# fm_transmitter.net
KiCad netlist of a schematic drawn in Altium Designer
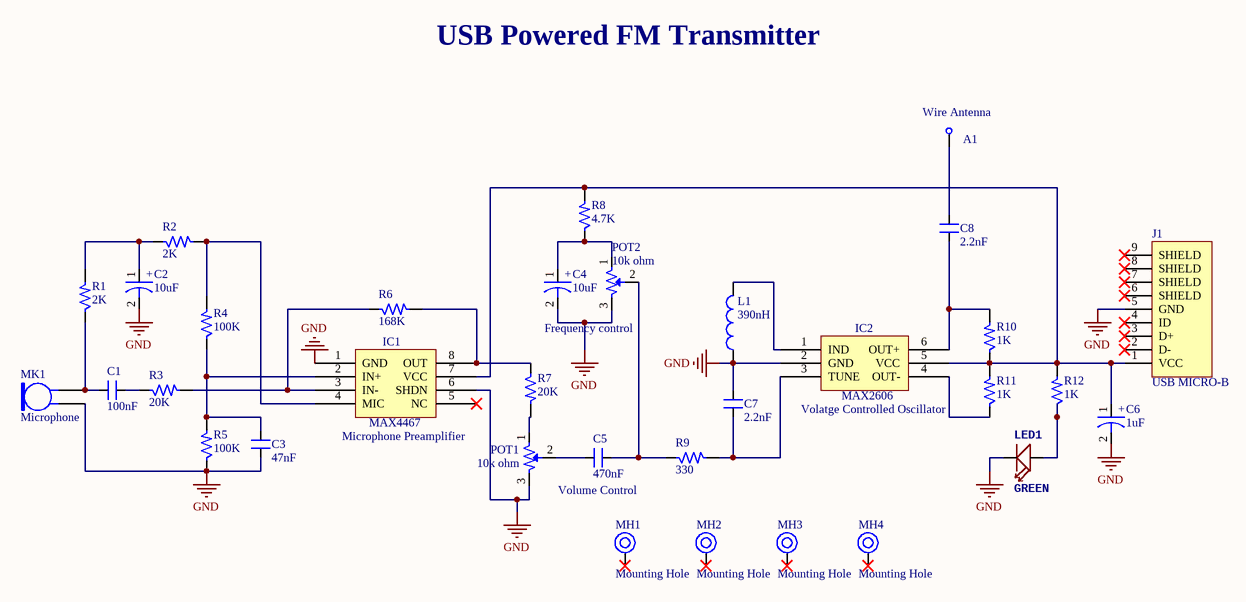
[diagram p0: fm_transmitter.SchDoc]

(export (version "E")
  (design (tool "Eeschema 10.0.6"))
  (components
    (comp (ref "A1")
      (value "Wire Antenna")
      (footprint "TEST POINT_78")
      (description "0.4mm hole size Test point")
      (fields (field (name "MANUFACTURER PART NUMBER") "NA"))
      (libsource (lib "ESTEEMPCBLIB") (part "TEST POINT"))
    )
    (comp (ref "C1")
      (value "100nF")
      (footprint "CAP_0805")
      (description "0.1µF ±10% 50V Ceramic Capacitor X7R 0805 (2012 Metric)")
      (fields
        (field (name "MANUFACTURER") "Samsung")
        (field (name "MANUFACTURER PART NUMBER") "CL21B104KBCNNNC")
      )
      (libsource (lib "ESTEEMPCBLIB") (part "CAP_0.1uF-50V-10%-0805"))
    )
    (comp (ref "C2")
      (value "10uF")
      (footprint "ACAP_P339_D393_H531_RAD")
      (description "10µF 400V Aluminum Electrolytic Capacitors Radial, Can - SMD 10000 Hrs @ 105°C")
      (fields
        (field (name "MANUFACTURER") "Nichicon")
        (field (name "MANUFACTURER PART NUMBER") "ULV2G100MNL1GS")
      )
      (libsource (lib "ESTEEMPCBLIB") (part "CAP-P_10uF-400V-20%-RAD"))
    )
    (comp (ref "C3")
      (value "47nF")
      (footprint "CAP_0805")
      (description "0.1µF ±10% 50V Ceramic Capacitor X7R 0805 (2012 Metric)")
      (fields
        (field (name "MANUFACTURER") "Samsung")
        (field (name "MANUFACTURER PART NUMBER") "CL21B104KBCNNNC")
      )
      (libsource (lib "ESTEEMPCBLIB") (part "CAP_0.1uF-50V-10%-0805"))
    )
    (comp (ref "C4")
      (value "10uF")
      (footprint "ACAP_P339_D393_H531_RAD")
      (description "10µF 400V Aluminum Electrolytic Capacitors Radial, Can - SMD 10000 Hrs @ 105°C")
      (fields
        (field (name "MANUFACTURER") "Nichicon")
        (field (name "MANUFACTURER PART NUMBER") "ULV2G100MNL1GS")
      )
      (libsource (lib "ESTEEMPCBLIB") (part "CAP-P_10uF-400V-20%-RAD"))
    )
    (comp (ref "C5")
      (value "470nF")
      (footprint "CAP_0805")
      (description "0.1µF ±10% 50V Ceramic Capacitor X7R 0805 (2012 Metric)")
      (fields
        (field (name "MANUFACTURER") "Samsung")
        (field (name "MANUFACTURER PART NUMBER") "CL21B104KBCNNNC")
      )
      (libsource (lib "ESTEEMPCBLIB") (part "CAP_0.1uF-50V-10%-0805"))
    )
    (comp (ref "C6")
      (value "1uF")
      (footprint "ACAP_P339_D393_H531_RAD")
      (description "10µF 400V Aluminum Electrolytic Capacitors Radial, Can - SMD 10000 Hrs @ 105°C")
      (fields
        (field (name "MANUFACTURER") "Nichicon")
        (field (name "MANUFACTURER PART NUMBER") "ULV2G100MNL1GS")
      )
      (libsource (lib "ESTEEMPCBLIB") (part "CAP-P_10uF-400V-20%-RAD"))
    )
    (comp (ref "C7")
      (value "2.2nF")
      (footprint "CAP_0805")
      (description "0.1µF ±10% 50V Ceramic Capacitor X7R 0805 (2012 Metric)")
      (fields
        (field (name "MANUFACTURER") "Samsung")
        (field (name "MANUFACTURER PART NUMBER") "CL21B104KBCNNNC")
      )
      (libsource (lib "ESTEEMPCBLIB") (part "CAP_0.1uF-50V-10%-0805"))
    )
    (comp (ref "C8")
      (value "2.2nF")
      (footprint "CAP_0805")
      (description "0.1µF ±10% 50V Ceramic Capacitor X7R 0805 (2012 Metric)")
      (fields
        (field (name "MANUFACTURER") "Samsung")
        (field (name "MANUFACTURER PART NUMBER") "CL21B104KBCNNNC")
      )
      (libsource (lib "ESTEEMPCBLIB") (part "CAP_0.1uF-50V-10%-0805"))
    )
    (comp (ref "IC1")
      (value "MAX4467")
      (footprint "TI SOT-23-8 DDF")
      (libsource (lib "MAX_ICs") (part "IC_MAX4467"))
    )
    (comp (ref "IC2")
      (value "MAX2606")
      (footprint "MAXIM SOT-23-6")
      (libsource (lib "MAX_ICs") (part "IC_MAX2606"))
    )
    (comp (ref "J1")
      (value "USB MICRO-B")
      (footprint "CON_10118192-0001LF_SMD")
      (description "USB - micro B USB 2.0 Receptacle Connector 5 Position Surface Mount, Right Angle")
      (fields (field (name "MANUFACTURER") "ICC") (field (name "MANUFACTURER PART NUMBER") "10118192-0001LF"))
      (libsource (lib "ESTEEMPCBLIB") (part "CON_USB2.0_MICROB-SMD"))
    )
    (comp (ref "L1")
      (value "390nH")
      (footprint "IND_0805")
      (description "Fixed Inductors MSS1583 SMT Power 0.038Ohms 33uH")
      (fields
        (field (name "MANUFACTURER") "Coilcraft")
        (field (name "MANUFACTURER PART NUMBER") "MSS1583-333MEB")
      )
      (libsource (lib "ESTEEMPCBLIB") (part "IND_33uH-8A-20%-SMD"))
    )
    (comp (ref "LED1")
      (value "GREEN")
      (footprint "LED-0603")
      (fields (field (name "MPN") "19-217-R6C-AL1M2VY-3T"))
      (libsource (lib "AltiumLibraryDDT") (part "LED-SMD-RED-DIFFUSED(0603)"))
    )
    (comp (ref "MH1")
      (value "Mounting Hole")
      (footprint "MOUNTING")
      (fields (field (name "MANUFACTURER PART NUMBER") "NA"))
      (libsource (lib "ESTEEMPCBLIB") (part "MH_3.5H_6D"))
    )
    (comp (ref "MH2")
      (value "Mounting Hole")
      (footprint "MOUNTING")
      (fields (field (name "MANUFACTURER PART NUMBER") "NA"))
      (libsource (lib "ESTEEMPCBLIB") (part "MH_3.5H_6D"))
    )
    (comp (ref "MH3")
      (value "Mounting Hole")
      (footprint "MOUNTING")
      (fields (field (name "MANUFACTURER PART NUMBER") "NA"))
      (libsource (lib "ESTEEMPCBLIB") (part "MH_3.5H_6D"))
    )
    (comp (ref "MH4")
      (value "Mounting Hole")
      (footprint "MOUNTING")
      (fields (field (name "MANUFACTURER PART NUMBER") "NA"))
      (libsource (lib "ESTEEMPCBLIB") (part "MH_3.5H_6D"))
    )
    (comp (ref "MK1")
      (value "Microphone")
      (footprint "PIN2")
      (fields (field (name "PUBLISHER") "Altium Limited"))
      (libsource (lib "Miscellaneous Devices") (part "Mic2"))
    )
    (comp (ref "POT1")
      (value "10k ohm")
      (footprint "POT_3361P_SMD")
      (description "10 kOhms 0.5W, 1/2W Gull Wing Surface Mount Trimmer Potentiometer Cermet 1 Turn Top Adjustment")
      (fields
        (field (name "MANUFACTURER") "Bourns")
        (field (name "MANUFACTURER PART NUMBER") "3361P-1-103GLF")
      )
      (libsource (lib "ESTEEMPCBLIB") (part "POT_10K-3361P-1-103GLF-SMD"))
    )
    (comp (ref "POT2")
      (value "10k ohm")
      (footprint "POT_3361P_SMD")
      (description "10 kOhms 0.5W, 1/2W Gull Wing Surface Mount Trimmer Potentiometer Cermet 1 Turn Top Adjustment")
      (fields
        (field (name "MANUFACTURER") "Bourns")
        (field (name "MANUFACTURER PART NUMBER") "3361P-1-103GLF")
      )
      (libsource (lib "ESTEEMPCBLIB") (part "POT_10K-3361P-1-103GLF-SMD"))
    )
    (comp (ref "R1")
      (value "2K")
      (footprint "RES_0805")
      (description "2 kOhms ±1% 0.125W, 1/8W Chip Resistor 0805 (2012 Metric) Moisture Resistant Thick Film")
      (fields
        (field (name "MANUFACTURER") "TE Connectivity")
        (field (name "MANUFACTURER PART NUMBER") "RC0805FR-072KL")
      )
      (libsource (lib "ESTEEMPCBLIB") (part "RES_2K-0.125W-1%-0805"))
    )
    (comp (ref "R2")
      (value "2K")
      (footprint "RES_0805")
      (description "2 kOhms ±1% 0.125W, 1/8W Chip Resistor 0805 (2012 Metric) Moisture Resistant Thick Film")
      (fields
        (field (name "MANUFACTURER") "TE Connectivity")
        (field (name "MANUFACTURER PART NUMBER") "RC0805FR-072KL")
      )
      (libsource (lib "ESTEEMPCBLIB") (part "RES_2K-0.125W-1%-0805"))
    )
    (comp (ref "R3")
      (value "20K")
      (footprint "RES_0805")
      (fields
        (field (name "MANUFACTURER") "Panasonic")
        (field (name "MANUFACTURER PART NUMBER") "ERJ-P06J203V")
      )
      (libsource (lib "ESTEEMPCBLIB") (part "RES_20K-0.5W-5%-0805"))
    )
    (comp (ref "R4")
      (value "100K")
      (footprint "RES_0805")
      (description "100 kOhms ±1% 0.125W, 1/8W Chip Resistor 0805 (2012 Metric) Automotive AEC-Q200 Thick Film")
      (fields (field (name "MANUFACTURER") "Walsin") (field (name "MANUFACTURER PART NUMBER") "WR08X1003FTL"))
      (libsource (lib "ESTEEMPCBLIB") (part "RES_100K-0.125W-1%-0805"))
    )
    (comp (ref "R5")
      (value "100K")
      (footprint "RES_0805")
      (description "100 kOhms ±1% 0.125W, 1/8W Chip Resistor 0805 (2012 Metric) Automotive AEC-Q200 Thick Film")
      (fields (field (name "MANUFACTURER") "Walsin") (field (name "MANUFACTURER PART NUMBER") "WR08X1003FTL"))
      (libsource (lib "ESTEEMPCBLIB") (part "RES_100K-0.125W-1%-0805"))
    )
    (comp (ref "R6")
      (value "168K")
      (footprint "RES_0805")
      (description "168 kOhms ±1% 0.125W, 1/8W Chip Resistor 0805 (2012 Metric) Automotive AEC-Q200 Thick Film")
      (fields (field (name "MANUFACTURER") "Walsin") (field (name "MANUFACTURER PART NUMBER") "WR08X1003FTL"))
      (libsource (lib "ESTEEMPCBLIB") (part "RES_100K-0.125W-1%-0805"))
    )
    (comp (ref "R7")
      (value "20K")
      (footprint "RES_0805")
      (fields
        (field (name "MANUFACTURER") "Panasonic")
        (field (name "MANUFACTURER PART NUMBER") "ERJ-P06J203V")
      )
      (libsource (lib "ESTEEMPCBLIB") (part "RES_20K-0.5W-5%-0805"))
    )
    (comp (ref "R8")
      (value "4.7K")
      (footprint "RES_0805")
      (description "4.7 kOhms ±1% 0.125W, 1/8W Chip Resistor 0805 (2012 Metric) Moisture Resistant Thick Film")
      (fields
        (field (name "MANUFACTURER") "TE Connectivity")
        (field (name "MANUFACTURER PART NUMBER") "RC0805FR-074K7L")
      )
      (libsource (lib "ESTEEMPCBLIB") (part "RES_4.7K-0.125W-1%-0805"))
    )
    (comp (ref "R9")
      (value "330")
      (footprint "RES_0805")
      (description "300 Ohms ±1% 0.125W, 1/8W Chip Resistor 0805 (2012 Metric) Thick Film")
      (fields (field (name "MANUFACTURER") "Panasonic") (field (name "MANUFACTURER PART NUMBER") "1623214-1"))
      (libsource (lib "ESTEEMPCBLIB") (part "RES_3.3K-0.125W-1%-0805"))
    )
    (comp (ref "R10")
      (value "1K")
      (footprint "RES_0805")
      (description "1 kOhms ±1% 0.125W, 1/8W Chip Resistor 0805 (2012 Metric) Moisture Resistant Thick Film")
      (fields (field (name "MANUFACTURER") "Walsin") (field (name "MANUFACTURER PART NUMBER") "WR08X1001FTL"))
      (libsource (lib "ESTEEMPCBLIB") (part "RES_1K-0.125W-1%-0805"))
    )
    (comp (ref "R11")
      (value "1K")
      (footprint "RES_0805")
      (description "10 kOhms ±1% 0.125W, 1/8W Chip Resistor 0805 (2012 Metric) Automotive AEC-Q200 Thick Film")
      (fields (field (name "MANUFACTURER") "CTS") (field (name "MANUFACTURER PART NUMBER") "WR08X1002FTL"))
      (libsource (lib "ESTEEMPCBLIB") (part "RES_10K-0.125W-1%-0805"))
    )
    (comp (ref "R12")
      (value "1K")
      (footprint "RES_0805")
      (description "1 kOhms ±1% 0.125W, 1/8W Chip Resistor 0805 (2012 Metric) Moisture Resistant Thick Film")
      (fields (field (name "MANUFACTURER") "Walsin") (field (name "MANUFACTURER PART NUMBER") "WR08X1001FTL"))
      (libsource (lib "ESTEEMPCBLIB") (part "RES_1K-0.125W-1%-0805"))
    )
  )
  (nets
    (net (code "1") (name "GND") (class "Default")
      (node (ref "C2") (pin "2") (pinfunction "2_2") (pintype "passive"))
      (node (ref "C3") (pin "1") (pinfunction "1_1") (pintype "passive"))
      (node (ref "C4") (pin "2") (pinfunction "2_2") (pintype "passive"))
      (node (ref "C6") (pin "2") (pinfunction "2_2") (pintype "passive"))
      (node (ref "C7") (pin "2") (pinfunction "2_2") (pintype "passive"))
      (node (ref "IC1") (pin "1") (pinfunction "GND_1") (pintype "passive"))
      (node (ref "IC1") (pin "6") (pinfunction "SHDN_6") (pintype "passive"))
      (node (ref "IC2") (pin "2") (pinfunction "GND_2") (pintype "passive"))
      (node (ref "J1") (pin "5") (pinfunction "GND_5") (pintype "passive"))
      (node (ref "L1") (pin "1") (pinfunction "1_1") (pintype "passive"))
      (node (ref "LED1") (pin "-") (pinfunction "-_-") (pintype "passive"))
      (node (ref "MK1") (pin "1") (pinfunction "1_1") (pintype "passive"))
      (node (ref "POT1") (pin "3") (pinfunction "3_3") (pintype "passive"))
      (node (ref "POT2") (pin "3") (pinfunction "3_3") (pintype "passive"))
      (node (ref "R5") (pin "1") (pinfunction "1_1") (pintype "passive"))
    )
    (net (code "2") (name "Net-(A1-Pad1)") (class "Default")
      (node (ref "A1") (pin "1") (pinfunction "1_1") (pintype "passive"))
      (node (ref "C8") (pin "2") (pinfunction "2_2") (pintype "passive"))
    )
    (net (code "3") (name "Net-(C1-Pad1)") (class "Default")
      (node (ref "C1") (pin "1") (pinfunction "1_1") (pintype "passive"))
      (node (ref "MK1") (pin "2") (pinfunction "2_2") (pintype "passive"))
      (node (ref "R1") (pin "1") (pinfunction "1_1") (pintype "passive"))
    )
    (net (code "4") (name "Net-(C1-Pad2)") (class "Default")
      (node (ref "C1") (pin "2") (pinfunction "2_2") (pintype "passive"))
      (node (ref "R3") (pin "1") (pinfunction "1_1") (pintype "passive"))
    )
    (net (code "5") (name "Net-(C2-Pad1)") (class "Default")
      (node (ref "C2") (pin "1") (pinfunction "1_1") (pintype "passive"))
      (node (ref "R1") (pin "2") (pinfunction "2_2") (pintype "passive"))
      (node (ref "R2") (pin "1") (pinfunction "1_1") (pintype "passive"))
    )
    (net (code "6") (name "Net-(C4-Pad1)") (class "Default")
      (node (ref "C4") (pin "1") (pinfunction "1_1") (pintype "passive"))
      (node (ref "POT2") (pin "1") (pinfunction "1_1") (pintype "passive"))
      (node (ref "R8") (pin "1") (pinfunction "1_1") (pintype "passive"))
    )
    (net (code "7") (name "Net-(C5-Pad1)") (class "Default")
      (node (ref "C5") (pin "1") (pinfunction "1_1") (pintype "passive"))
      (node (ref "POT1") (pin "2") (pinfunction "2_2") (pintype "passive"))
    )
    (net (code "8") (name "Net-(C5-Pad2)") (class "Default")
      (node (ref "C5") (pin "2") (pinfunction "2_2") (pintype "passive"))
      (node (ref "POT2") (pin "2") (pinfunction "2_2") (pintype "passive"))
      (node (ref "R9") (pin "1") (pinfunction "1_1") (pintype "passive"))
    )
    (net (code "9") (name "Net-(IC1-IN+)") (class "Default")
      (node (ref "C3") (pin "2") (pinfunction "2_2") (pintype "passive"))
      (node (ref "IC1") (pin "2") (pinfunction "IN+_2") (pintype "passive"))
      (node (ref "R4") (pin "1") (pinfunction "1_1") (pintype "passive"))
      (node (ref "R5") (pin "2") (pinfunction "2_2") (pintype "passive"))
    )
    (net (code "10") (name "Net-(IC1-IN-)") (class "Default")
      (node (ref "IC1") (pin "3") (pinfunction "IN-_3") (pintype "passive"))
      (node (ref "R3") (pin "2") (pinfunction "2_2") (pintype "passive"))
      (node (ref "R6") (pin "1") (pinfunction "1_1") (pintype "passive"))
    )
    (net (code "11") (name "Net-(IC1-MIC)") (class "Default")
      (node (ref "IC1") (pin "4") (pinfunction "MIC_4") (pintype "passive"))
      (node (ref "R2") (pin "2") (pinfunction "2_2") (pintype "passive"))
      (node (ref "R4") (pin "2") (pinfunction "2_2") (pintype "passive"))
    )
    (net (code "12") (name "Net-(IC1-OUT)") (class "Default")
      (node (ref "IC1") (pin "8") (pinfunction "OUT_8") (pintype "passive"))
      (node (ref "R6") (pin "2") (pinfunction "2_2") (pintype "passive"))
      (node (ref "R7") (pin "1") (pinfunction "1_1") (pintype "passive"))
    )
    (net (code "13") (name "Net-(IC1-VCC)") (class "Default")
      (node (ref "C6") (pin "1") (pinfunction "1_1") (pintype "passive"))
      (node (ref "IC1") (pin "7") (pinfunction "VCC_7") (pintype "passive"))
      (node (ref "IC2") (pin "5") (pinfunction "VCC_5") (pintype "passive"))
      (node (ref "J1") (pin "1") (pinfunction "VCC_1") (pintype "passive"))
      (node (ref "R10") (pin "1") (pinfunction "1_1") (pintype "passive"))
      (node (ref "R11") (pin "2") (pinfunction "2_2") (pintype "passive"))
      (node (ref "R12") (pin "2") (pinfunction "2_2") (pintype "passive"))
      (node (ref "R8") (pin "2") (pinfunction "2_2") (pintype "passive"))
    )
    (net (code "14") (name "Net-(IC2-IND)") (class "Default")
      (node (ref "IC2") (pin "1") (pinfunction "IND_1") (pintype "passive"))
      (node (ref "L1") (pin "2") (pinfunction "2_2") (pintype "passive"))
    )
    (net (code "15") (name "Net-(IC2-OUT+)") (class "Default")
      (node (ref "C8") (pin "1") (pinfunction "1_1") (pintype "passive"))
      (node (ref "IC2") (pin "6") (pinfunction "OUT+_6") (pintype "passive"))
      (node (ref "R10") (pin "2") (pinfunction "2_2") (pintype "passive"))
    )
    (net (code "16") (name "Net-(IC2-OUT-)") (class "Default")
      (node (ref "IC2") (pin "4") (pinfunction "OUT-_4") (pintype "passive"))
      (node (ref "R11") (pin "1") (pinfunction "1_1") (pintype "passive"))
    )
    (net (code "17") (name "Net-(IC2-TUNE)") (class "Default")
      (node (ref "C7") (pin "1") (pinfunction "1_1") (pintype "passive"))
      (node (ref "IC2") (pin "3") (pinfunction "TUNE_3") (pintype "passive"))
      (node (ref "R9") (pin "2") (pinfunction "2_2") (pintype "passive"))
    )
    (net (code "18") (name "Net-(LED1-Pad+)") (class "Default")
      (node (ref "LED1") (pin "+") (pinfunction "+_+") (pintype "passive"))
      (node (ref "R12") (pin "1") (pinfunction "1_1") (pintype "passive"))
    )
    (net (code "19") (name "Net-(POT1-Pad1)") (class "Default")
      (node (ref "POT1") (pin "1") (pinfunction "1_1") (pintype "passive"))
      (node (ref "R7") (pin "2") (pinfunction "2_2") (pintype "passive"))
    )
    (net (code "20") (name "unconnected-(IC1-NC-Pad5)") (class "Default")
      (node (ref "IC1") (pin "5") (pinfunction "NC_5") (pintype "passive+no_connect"))
    )
    (net (code "21") (name "unconnected-(J1-D+-Pad3)") (class "Default")
      (node (ref "J1") (pin "3") (pinfunction "D+_3") (pintype "passive+no_connect"))
    )
    (net (code "22") (name "unconnected-(J1-D--Pad2)") (class "Default")
      (node (ref "J1") (pin "2") (pinfunction "D-_2") (pintype "passive+no_connect"))
    )
    (net (code "23") (name "unconnected-(J1-ID-Pad4)") (class "Default")
      (node (ref "J1") (pin "4") (pinfunction "ID_4") (pintype "passive+no_connect"))
    )
    (net (code "24") (name "unconnected-(J1-SHIELD-Pad6)") (class "Default")
      (node (ref "J1") (pin "6") (pinfunction "SHIELD_6") (pintype "passive+no_connect"))
    )
    (net (code "25") (name "unconnected-(J1-SHIELD-Pad7)") (class "Default")
      (node (ref "J1") (pin "7") (pinfunction "SHIELD_7") (pintype "passive+no_connect"))
    )
    (net (code "26") (name "unconnected-(J1-SHIELD-Pad8)") (class "Default")
      (node (ref "J1") (pin "8") (pinfunction "SHIELD_8") (pintype "passive+no_connect"))
    )
    (net (code "27") (name "unconnected-(J1-SHIELD-Pad9)") (class "Default")
      (node (ref "J1") (pin "9") (pinfunction "SHIELD_9") (pintype "passive+no_connect"))
    )
    (net (code "28") (name "unconnected-(MH1-Pad1)") (class "Default")
      (node (ref "MH1") (pin "1") (pinfunction "1_1") (pintype "passive+no_connect"))
    )
    (net (code "29") (name "unconnected-(MH2-Pad1)") (class "Default")
      (node (ref "MH2") (pin "1") (pinfunction "1_1") (pintype "passive+no_connect"))
    )
    (net (code "30") (name "unconnected-(MH3-Pad1)") (class "Default")
      (node (ref "MH3") (pin "1") (pinfunction "1_1") (pintype "passive+no_connect"))
    )
    (net (code "31") (name "unconnected-(MH4-Pad1)") (class "Default")
      (node (ref "MH4") (pin "1") (pinfunction "1_1") (pintype "passive+no_connect"))
    )
  )
)
